# zmpt101b_-_3phase_din_v0_2.net
KiCad netlist of a schematic drawn in EAGLE
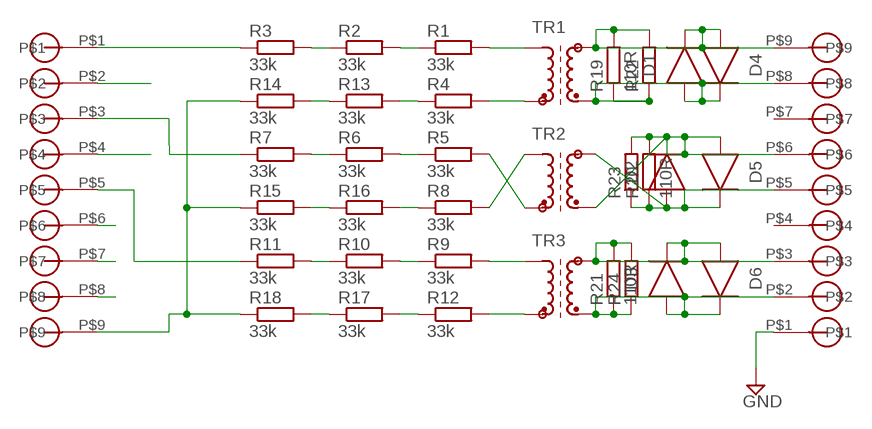
[diagram p0: schematic, sheet 1]

(export (version "E")
  (design (tool "Eeschema 10.0.6"))
  (components
    (comp (ref "D1")
      (value "DIODE_DO-219-AB(SOD123F)")
      (footprint "eagle-import:SODFL3718X115")
      (libsource (lib "eagle-import") (part "DIODEDO-219-AB(SOD123F)_"))
    )
    (comp (ref "D2")
      (value "DIODE_DO-219-AB(SOD123F)")
      (footprint "eagle-import:SODFL3718X115")
      (libsource (lib "eagle-import") (part "DIODEDO-219-AB(SOD123F)_"))
    )
    (comp (ref "D3")
      (value "DIODE_DO-219-AB(SOD123F)")
      (footprint "eagle-import:SODFL3718X115")
      (libsource (lib "eagle-import") (part "DIODEDO-219-AB(SOD123F)_"))
    )
    (comp (ref "D4")
      (value "DIODE_DO-219-AB(SOD123F)")
      (footprint "eagle-import:SODFL3718X115")
      (libsource (lib "eagle-import") (part "DIODEDO-219-AB(SOD123F)_"))
    )
    (comp (ref "D5")
      (value "DIODE_DO-219-AB(SOD123F)")
      (footprint "eagle-import:SODFL3718X115")
      (libsource (lib "eagle-import") (part "DIODEDO-219-AB(SOD123F)_"))
    )
    (comp (ref "D6")
      (value "DIODE_DO-219-AB(SOD123F)")
      (footprint "eagle-import:SODFL3718X115")
      (libsource (lib "eagle-import") (part "DIODEDO-219-AB(SOD123F)_"))
    )
    (comp (ref "R1")
      (value "33k")
      (footprint "eagle-import:R0603")
      (libsource (lib "eagle-import") (part "R-EU_R0603"))
    )
    (comp (ref "R2")
      (value "33k")
      (footprint "eagle-import:R0603")
      (libsource (lib "eagle-import") (part "R-EU_R0603"))
    )
    (comp (ref "R3")
      (value "33k")
      (footprint "eagle-import:R0603")
      (libsource (lib "eagle-import") (part "R-EU_R0603"))
    )
    (comp (ref "R4")
      (value "33k")
      (footprint "eagle-import:R0603")
      (libsource (lib "eagle-import") (part "R-EU_R0603"))
    )
    (comp (ref "R5")
      (value "33k")
      (footprint "eagle-import:R0603")
      (libsource (lib "eagle-import") (part "R-EU_R0603"))
    )
    (comp (ref "R6")
      (value "33k")
      (footprint "eagle-import:R0603")
      (libsource (lib "eagle-import") (part "R-EU_R0603"))
    )
    (comp (ref "R7")
      (value "33k")
      (footprint "eagle-import:R0603")
      (libsource (lib "eagle-import") (part "R-EU_R0603"))
    )
    (comp (ref "R8")
      (value "33k")
      (footprint "eagle-import:R0603")
      (libsource (lib "eagle-import") (part "R-EU_R0603"))
    )
    (comp (ref "R9")
      (value "33k")
      (footprint "eagle-import:R0603")
      (libsource (lib "eagle-import") (part "R-EU_R0603"))
    )
    (comp (ref "R10")
      (value "33k")
      (footprint "eagle-import:R0603")
      (libsource (lib "eagle-import") (part "R-EU_R0603"))
    )
    (comp (ref "R11")
      (value "33k")
      (footprint "eagle-import:R0603")
      (libsource (lib "eagle-import") (part "R-EU_R0603"))
    )
    (comp (ref "R12")
      (value "33k")
      (footprint "eagle-import:R0603")
      (libsource (lib "eagle-import") (part "R-EU_R0603"))
    )
    (comp (ref "R13")
      (value "33k")
      (footprint "eagle-import:R0603")
      (libsource (lib "eagle-import") (part "R-EU_R0603"))
    )
    (comp (ref "R14")
      (value "33k")
      (footprint "eagle-import:R0603")
      (libsource (lib "eagle-import") (part "R-EU_R0603"))
    )
    (comp (ref "R15")
      (value "33k")
      (footprint "eagle-import:R0603")
      (libsource (lib "eagle-import") (part "R-EU_R0603"))
    )
    (comp (ref "R16")
      (value "33k")
      (footprint "eagle-import:R0603")
      (libsource (lib "eagle-import") (part "R-EU_R0603"))
    )
    (comp (ref "R17")
      (value "33k")
      (footprint "eagle-import:R0603")
      (libsource (lib "eagle-import") (part "R-EU_R0603"))
    )
    (comp (ref "R18")
      (value "33k")
      (footprint "eagle-import:R0603")
      (libsource (lib "eagle-import") (part "R-EU_R0603"))
    )
    (comp (ref "R19")
      (value "110R")
      (footprint "eagle-import:R0603")
      (libsource (lib "eagle-import") (part "R-EU_R0603"))
    )
    (comp (ref "R20")
      (value "110R")
      (footprint "eagle-import:R0603")
      (libsource (lib "eagle-import") (part "R-EU_R0603"))
    )
    (comp (ref "R21")
      (value "110R")
      (footprint "eagle-import:R0603")
      (libsource (lib "eagle-import") (part "R-EU_R0603"))
    )
    (comp (ref "R22")
      (value "R-EU_0207/12")
      (footprint "eagle-import:0207_12")
      (libsource (lib "eagle-import") (part "R-EU_0207/12"))
    )
    (comp (ref "R23")
      (value "R-EU_0207/12")
      (footprint "eagle-import:0207_12")
      (libsource (lib "eagle-import") (part "R-EU_0207/12"))
    )
    (comp (ref "R24")
      (value "R-EU_0207/12")
      (footprint "eagle-import:0207_12")
      (libsource (lib "eagle-import") (part "R-EU_0207/12"))
    )
    (comp (ref "TR1")
      (value "ZMPT101B")
      (footprint "eagle-import:ZMPT101B")
      (libsource (lib "eagle-import") (part "ZMPT101B"))
    )
    (comp (ref "TR2")
      (value "ZMPT101B")
      (footprint "eagle-import:ZMPT101B")
      (libsource (lib "eagle-import") (part "ZMPT101B"))
    )
    (comp (ref "TR3")
      (value "ZMPT101B")
      (footprint "eagle-import:ZMPT101B")
      (libsource (lib "eagle-import") (part "ZMPT101B"))
    )
    (comp (ref "U$1")
      (value "5MMBLOCK_X9")
      (footprint "eagle-import:9_5.08")
      (libsource (lib "eagle-import") (part "5MMBLOCK_X9"))
    )
    (comp (ref "U$2")
      (value "5MMBLOCK_X9")
      (footprint "eagle-import:9_5.08")
      (libsource (lib "eagle-import") (part "5MMBLOCK_X9"))
    )
  )
  (nets
    (net (code "1") (name "/P$4") (class "Default")
      (node (ref "U$2") (pin "P$4") (pinfunction "P$4_P$4") (pintype "power_in"))
    )
    (net (code "2") (name "/P$7") (class "Default")
      (node (ref "U$2") (pin "P$7") (pinfunction "P$7_P$7") (pintype "power_in"))
    )
    (net (code "3") (name "GND") (class "Default")
      (node (ref "U$2") (pin "P$1") (pinfunction "P$1_P$1") (pintype "power_in"))
    )
    (net (code "4") (name "Net-(D1-A)") (class "Default")
      (node (ref "D1") (pin "2") (pinfunction "A_2") (pintype "passive"))
      (node (ref "D4") (pin "1") (pinfunction "C_1") (pintype "passive"))
      (node (ref "R19") (pin "1") (pinfunction "1_1") (pintype "passive"))
      (node (ref "R22") (pin "1") (pinfunction "1_1") (pintype "passive"))
      (node (ref "TR1") (pin "P$2") (pinfunction "E2_P$2") (pintype "passive"))
      (node (ref "U$2") (pin "P$8") (pinfunction "P$8_P$8") (pintype "power_in"))
    )
    (net (code "5") (name "Net-(D1-C)") (class "Default")
      (node (ref "D1") (pin "1") (pinfunction "C_1") (pintype "passive"))
      (node (ref "D4") (pin "2") (pinfunction "A_2") (pintype "passive"))
      (node (ref "R19") (pin "2") (pinfunction "2_2") (pintype "passive"))
      (node (ref "R22") (pin "2") (pinfunction "2_2") (pintype "passive"))
      (node (ref "TR1") (pin "P$1") (pinfunction "A2_P$1") (pintype "passive"))
      (node (ref "U$2") (pin "P$9") (pinfunction "P$9_P$9") (pintype "power_in"))
    )
    (net (code "6") (name "Net-(D2-A)") (class "Default")
      (node (ref "D2") (pin "2") (pinfunction "A_2") (pintype "passive"))
      (node (ref "D5") (pin "1") (pinfunction "C_1") (pintype "passive"))
      (node (ref "R20") (pin "1") (pinfunction "1_1") (pintype "passive"))
      (node (ref "R23") (pin "1") (pinfunction "1_1") (pintype "passive"))
      (node (ref "TR2") (pin "P$1") (pinfunction "A2_P$1") (pintype "passive"))
      (node (ref "U$2") (pin "P$5") (pinfunction "P$5_P$5") (pintype "power_in"))
    )
    (net (code "7") (name "Net-(D2-C)") (class "Default")
      (node (ref "D2") (pin "1") (pinfunction "C_1") (pintype "passive"))
      (node (ref "D5") (pin "2") (pinfunction "A_2") (pintype "passive"))
      (node (ref "R20") (pin "2") (pinfunction "2_2") (pintype "passive"))
      (node (ref "R23") (pin "2") (pinfunction "2_2") (pintype "passive"))
      (node (ref "TR2") (pin "P$2") (pinfunction "E2_P$2") (pintype "passive"))
      (node (ref "U$2") (pin "P$6") (pinfunction "P$6_P$6") (pintype "power_in"))
    )
    (net (code "8") (name "Net-(D3-A)") (class "Default")
      (node (ref "D3") (pin "2") (pinfunction "A_2") (pintype "passive"))
      (node (ref "D6") (pin "1") (pinfunction "C_1") (pintype "passive"))
      (node (ref "R21") (pin "1") (pinfunction "1_1") (pintype "passive"))
      (node (ref "R24") (pin "1") (pinfunction "1_1") (pintype "passive"))
      (node (ref "TR3") (pin "P$2") (pinfunction "E2_P$2") (pintype "passive"))
      (node (ref "U$2") (pin "P$2") (pinfunction "P$2_P$2") (pintype "power_in"))
    )
    (net (code "9") (name "Net-(D3-C)") (class "Default")
      (node (ref "D3") (pin "1") (pinfunction "C_1") (pintype "passive"))
      (node (ref "D6") (pin "2") (pinfunction "A_2") (pintype "passive"))
      (node (ref "R21") (pin "2") (pinfunction "2_2") (pintype "passive"))
      (node (ref "R24") (pin "2") (pinfunction "2_2") (pintype "passive"))
      (node (ref "TR3") (pin "P$1") (pinfunction "A2_P$1") (pintype "passive"))
      (node (ref "U$2") (pin "P$3") (pinfunction "P$3_P$3") (pintype "power_in"))
    )
    (net (code "10") (name "Net-(R1-Pad1)") (class "Default")
      (node (ref "R1") (pin "1") (pinfunction "1_1") (pintype "passive"))
      (node (ref "R2") (pin "2") (pinfunction "2_2") (pintype "passive"))
    )
    (net (code "11") (name "Net-(R2-Pad1)") (class "Default")
      (node (ref "R2") (pin "1") (pinfunction "1_1") (pintype "passive"))
      (node (ref "R3") (pin "2") (pinfunction "2_2") (pintype "passive"))
    )
    (net (code "12") (name "Net-(R3-Pad1)") (class "Default")
      (node (ref "R3") (pin "1") (pinfunction "1_1") (pintype "passive"))
      (node (ref "U$1") (pin "P$1") (pinfunction "P$1_P$1") (pintype "power_in"))
    )
    (net (code "13") (name "Net-(R5-Pad1)") (class "Default")
      (node (ref "R5") (pin "1") (pinfunction "1_1") (pintype "passive"))
      (node (ref "R6") (pin "2") (pinfunction "2_2") (pintype "passive"))
    )
    (net (code "14") (name "Net-(R6-Pad1)") (class "Default")
      (node (ref "R6") (pin "1") (pinfunction "1_1") (pintype "passive"))
      (node (ref "R7") (pin "2") (pinfunction "2_2") (pintype "passive"))
    )
    (net (code "15") (name "Net-(R7-Pad1)") (class "Default")
      (node (ref "R7") (pin "1") (pinfunction "1_1") (pintype "passive"))
      (node (ref "U$1") (pin "P$3") (pinfunction "P$3_P$3") (pintype "power_in"))
    )
    (net (code "16") (name "Net-(R10-Pad1)") (class "Default")
      (node (ref "R10") (pin "1") (pinfunction "1_1") (pintype "passive"))
      (node (ref "R11") (pin "2") (pinfunction "2_2") (pintype "passive"))
    )
    (net (code "17") (name "Net-(R10-Pad2)") (class "Default")
      (node (ref "R10") (pin "2") (pinfunction "2_2") (pintype "passive"))
      (node (ref "R9") (pin "1") (pinfunction "1_1") (pintype "passive"))
    )
    (net (code "18") (name "Net-(R11-Pad1)") (class "Default")
      (node (ref "R11") (pin "1") (pinfunction "1_1") (pintype "passive"))
      (node (ref "U$1") (pin "P$5") (pinfunction "P$5_P$5") (pintype "power_in"))
    )
    (net (code "19") (name "Net-(R12-Pad1)") (class "Default")
      (node (ref "R12") (pin "1") (pinfunction "1_1") (pintype "passive"))
      (node (ref "R17") (pin "2") (pinfunction "2_2") (pintype "passive"))
    )
    (net (code "20") (name "Net-(R13-Pad1)") (class "Default")
      (node (ref "R13") (pin "1") (pinfunction "1_1") (pintype "passive"))
      (node (ref "R14") (pin "2") (pinfunction "2_2") (pintype "passive"))
    )
    (net (code "21") (name "Net-(R13-Pad2)") (class "Default")
      (node (ref "R13") (pin "2") (pinfunction "2_2") (pintype "passive"))
      (node (ref "R4") (pin "1") (pinfunction "1_1") (pintype "passive"))
    )
    (net (code "22") (name "Net-(R14-Pad1)") (class "Default")
      (node (ref "R14") (pin "1") (pinfunction "1_1") (pintype "passive"))
      (node (ref "R15") (pin "1") (pinfunction "1_1") (pintype "passive"))
      (node (ref "R18") (pin "1") (pinfunction "1_1") (pintype "passive"))
      (node (ref "U$1") (pin "P$9") (pinfunction "P$9_P$9") (pintype "power_in"))
    )
    (net (code "23") (name "Net-(R15-Pad2)") (class "Default")
      (node (ref "R15") (pin "2") (pinfunction "2_2") (pintype "passive"))
      (node (ref "R16") (pin "1") (pinfunction "1_1") (pintype "passive"))
    )
    (net (code "24") (name "Net-(R16-Pad2)") (class "Default")
      (node (ref "R16") (pin "2") (pinfunction "2_2") (pintype "passive"))
      (node (ref "R8") (pin "1") (pinfunction "1_1") (pintype "passive"))
    )
    (net (code "25") (name "Net-(R17-Pad1)") (class "Default")
      (node (ref "R17") (pin "1") (pinfunction "1_1") (pintype "passive"))
      (node (ref "R18") (pin "2") (pinfunction "2_2") (pintype "passive"))
    )
    (net (code "26") (name "Net-(TR1-A1)") (class "Default")
      (node (ref "R1") (pin "2") (pinfunction "2_2") (pintype "passive"))
      (node (ref "TR1") (pin "P$4") (pinfunction "A1_P$4") (pintype "passive"))
    )
    (net (code "27") (name "Net-(TR1-E1)") (class "Default")
      (node (ref "R4") (pin "2") (pinfunction "2_2") (pintype "passive"))
      (node (ref "TR1") (pin "P$3") (pinfunction "E1_P$3") (pintype "passive"))
    )
    (net (code "28") (name "Net-(TR2-A1)") (class "Default")
      (node (ref "R8") (pin "2") (pinfunction "2_2") (pintype "passive"))
      (node (ref "TR2") (pin "P$4") (pinfunction "A1_P$4") (pintype "passive"))
    )
    (net (code "29") (name "Net-(TR2-E1)") (class "Default")
      (node (ref "R5") (pin "2") (pinfunction "2_2") (pintype "passive"))
      (node (ref "TR2") (pin "P$3") (pinfunction "E1_P$3") (pintype "passive"))
    )
    (net (code "30") (name "Net-(TR3-A1)") (class "Default")
      (node (ref "R9") (pin "2") (pinfunction "2_2") (pintype "passive"))
      (node (ref "TR3") (pin "P$4") (pinfunction "A1_P$4") (pintype "passive"))
    )
    (net (code "31") (name "Net-(TR3-E1)") (class "Default")
      (node (ref "R12") (pin "2") (pinfunction "2_2") (pintype "passive"))
      (node (ref "TR3") (pin "P$3") (pinfunction "E1_P$3") (pintype "passive"))
    )
    (net (code "32") (name "unconnected-(U$1-PadP$2)") (class "Default")
      (node (ref "U$1") (pin "P$2") (pinfunction "P$2_P$2") (pintype "power_in"))
    )
    (net (code "33") (name "unconnected-(U$1-PadP$4)") (class "Default")
      (node (ref "U$1") (pin "P$4") (pinfunction "P$4_P$4") (pintype "power_in"))
    )
    (net (code "34") (name "unconnected-(U$1-PadP$6)") (class "Default")
      (node (ref "U$1") (pin "P$6") (pinfunction "P$6_P$6") (pintype "power_in"))
    )
    (net (code "35") (name "unconnected-(U$1-PadP$7)") (class "Default")
      (node (ref "U$1") (pin "P$7") (pinfunction "P$7_P$7") (pintype "power_in"))
    )
    (net (code "36") (name "unconnected-(U$1-PadP$8)") (class "Default")
      (node (ref "U$1") (pin "P$8") (pinfunction "P$8_P$8") (pintype "power_in"))
    )
  )
)
